# NE555.net
KiCad netlist of a schematic drawn in Altium Designer
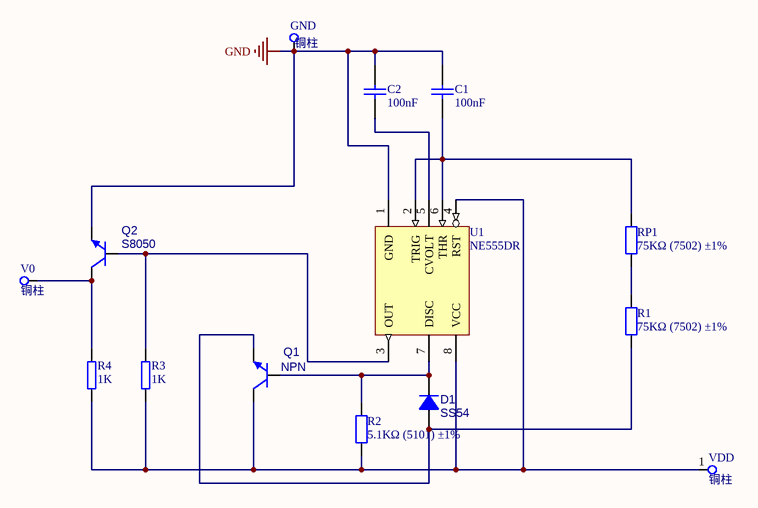
[diagram p0: NE555.SchDoc]

(export (version "E")
  (design (tool "Eeschema 10.0.6"))
  (components
    (comp (ref "C1")
      (value "100nF")
      (footprint "HDR1X2")
      (description "贴片电容")
      (fields
        (field (name "VOLTAGE") "50V")
        (field (name "TOLERANCE") "±10%")
        (field (name "PUBLISHER") "Altium Limited")
      )
      (libsource (lib "DRV8701E 双驱V1.1 集成封装库") (part "Cap-Chip_1"))
    )
    (comp (ref "C2")
      (value "100nF")
      (footprint "CAPC1608[0603]S-N")
      (description "贴片电容")
      (fields
        (field (name "VOLTAGE") "50V")
        (field (name "TOLERANCE") "±10%")
        (field (name "PUBLISHER") "Altium Limited")
      )
      (libsource (lib "DRV8701E 双驱V1.1 集成封装库") (part "Cap-Chip_1"))
    )
    (comp (ref "D1")
      (value "SS54")
      (footprint "SMA[DO-214AC]")
      (description "普通二极管 Diode")
      (fields (field (name "PUBLISHER") "Altium Limited"))
      (libsource (lib "TC264 主板V2.3 集成封装库") (part "Diode"))
    )
    (comp (ref "GND")
      (value "铜柱")
      (footprint "铜柱")
      (description "2.1mm")
      (libsource (lib "Module") (part "铜柱"))
    )
    (comp (ref "Q1")
      (value "NPN")
      (footprint "SOT-23")
      (description "Discrete NPN Bipolar Transistor")
      (fields (field (name "PARTNUMBER") "NPN") (field (name "PUBLISHER") "Altium Limited"))
      (libsource (lib "TC264 主板V2.3 集成封装库") (part "NPN S8050"))
    )
    (comp (ref "Q2")
      (value "S8050")
      (footprint "SOT-23")
      (description "Discrete NPN Bipolar Transistor")
      (fields (field (name "PARTNUMBER") "S8050") (field (name "PUBLISHER") "Altium Limited"))
      (libsource (lib "TC264 主板V2.3 集成封装库") (part "NPN S8050"))
    )
    (comp (ref "R1")
      (value "75KΩ (7502) ±1%")
      (footprint "RESC1608[0603]S-N")
      (description "贴片电阻")
      (libsource (lib "RES") (part "0603 75KΩ (7502) 1%"))
    )
    (comp (ref "R2")
      (value "5.1KΩ (5101) ±1%")
      (footprint "RESC1608[0603]S-N")
      (description "贴片电阻")
      (libsource (lib "RES") (part "0603 5.1KΩ (5101) 1%"))
    )
    (comp (ref "R3")
      (value "1K")
      (footprint "RESC1608[0603]S-N")
      (description "贴片电阻")
      (fields
        (field (name "TOLERANCE") "±1%")
        (field (name "Comment") "1K ±1%")
        (field (name "PUBLISHER") "Altium Limited")
      )
      (libsource (lib "DRV8701E 双驱V1.1 集成封装库") (part "Res-Chip_2"))
    )
    (comp (ref "R4")
      (value "1K")
      (footprint "RESC1608[0603]S-N")
      (description "贴片电阻")
      (fields
        (field (name "TOLERANCE") "±1%")
        (field (name "Comment") "1K ±1%")
        (field (name "PUBLISHER") "Altium Limited")
      )
      (libsource (lib "DRV8701E 双驱V1.1 集成封装库") (part "Res-Chip_2"))
    )
    (comp (ref "RP1")
      (value "75KΩ (7502) ±1%")
      (footprint "RESC1608[0603]S-N")
      (description "贴片电阻")
      (libsource (lib "RES") (part "0603 75KΩ (7502) 1%"))
    )
    (comp (ref "U1")
      (value "NE555DR")
      (footprint "NE555DR")
      (description "时基集成")
      (libsource (lib "IC") (part "NE555DR_[C7593]"))
    )
    (comp (ref "V0")
      (value "铜柱")
      (footprint "铜柱")
      (description "2.1mm")
      (libsource (lib "Module") (part "铜柱"))
    )
    (comp (ref "VDD") (value "铜柱") (footprint "铜柱") (description "2.1mm") (libsource (lib "") (part "铜柱_1")))
  )
  (nets
    (net (code "1") (name "GND") (class "Default")
      (node (ref "C1") (pin "2") (pinfunction "2_2") (pintype "passive"))
      (node (ref "C2") (pin "1") (pinfunction "1_1") (pintype "passive"))
      (node (ref "GND") (pin "1") (pintype "passive"))
      (node (ref "Q2") (pin "2") (pinfunction "E_2") (pintype "passive"))
      (node (ref "U1") (pin "1") (pinfunction "GND_1") (pintype "power_in"))
    )
    (net (code "2") (name "Net-(Q1-B)") (class "Default")
      (node (ref "D1") (pin "K") (pinfunction "K_K") (pintype "passive"))
      (node (ref "Q1") (pin "1") (pinfunction "B_1") (pintype "passive"))
      (node (ref "R2") (pin "2") (pinfunction "2_2") (pintype "passive"))
      (node (ref "U1") (pin "7") (pinfunction "DISC_7") (pintype "open_collector"))
    )
    (net (code "3") (name "Net-(Q1-C)") (class "Default")
      (node (ref "Q1") (pin "3") (pinfunction "C_3") (pintype "passive"))
      (node (ref "R2") (pin "1") (pinfunction "1_1") (pintype "passive"))
      (node (ref "R3") (pin "1") (pinfunction "1_1") (pintype "passive"))
      (node (ref "R4") (pin "1") (pinfunction "1_1") (pintype "passive"))
      (node (ref "U1") (pin "4") (pinfunction "RST_4") (pintype "input"))
      (node (ref "U1") (pin "8") (pinfunction "VCC_8") (pintype "power_in"))
      (node (ref "VDD") (pin "1") (pintype "passive"))
    )
    (net (code "4") (name "Net-(Q1-E)") (class "Default")
      (node (ref "D1") (pin "A") (pinfunction "A_A") (pintype "passive"))
      (node (ref "Q1") (pin "2") (pinfunction "E_2") (pintype "passive"))
      (node (ref "R1") (pin "1") (pinfunction "1_1") (pintype "passive"))
    )
    (net (code "5") (name "Net-(Q2-B)") (class "Default")
      (node (ref "Q2") (pin "1") (pinfunction "B_1") (pintype "passive"))
      (node (ref "R3") (pin "2") (pinfunction "2_2") (pintype "passive"))
      (node (ref "U1") (pin "3") (pinfunction "OUT_3") (pintype "output"))
    )
    (net (code "6") (name "Net-(Q2-C)") (class "Default")
      (node (ref "Q2") (pin "3") (pinfunction "C_3") (pintype "passive"))
      (node (ref "R4") (pin "2") (pinfunction "2_2") (pintype "passive"))
      (node (ref "V0") (pin "1") (pintype "passive"))
    )
    (net (code "7") (name "Net-(R1-Pad2)") (class "Default")
      (node (ref "R1") (pin "2") (pinfunction "2_2") (pintype "passive"))
      (node (ref "RP1") (pin "1") (pinfunction "1_1") (pintype "passive"))
    )
    (net (code "8") (name "Net-(U1-CVOLT)") (class "Default")
      (node (ref "C2") (pin "2") (pinfunction "2_2") (pintype "passive"))
      (node (ref "U1") (pin "5") (pinfunction "CVOLT_5") (pintype "passive"))
    )
    (net (code "9") (name "Net-(U1-THR)") (class "Default")
      (node (ref "C1") (pin "1") (pinfunction "1_1") (pintype "passive"))
      (node (ref "RP1") (pin "2") (pinfunction "2_2") (pintype "passive"))
      (node (ref "U1") (pin "2") (pinfunction "TRIG_2") (pintype "input"))
      (node (ref "U1") (pin "6") (pinfunction "THR_6") (pintype "input"))
    )
  )
)
